# 555-light-buzzer.net
KiCad netlist of a schematic drawn in EAGLE
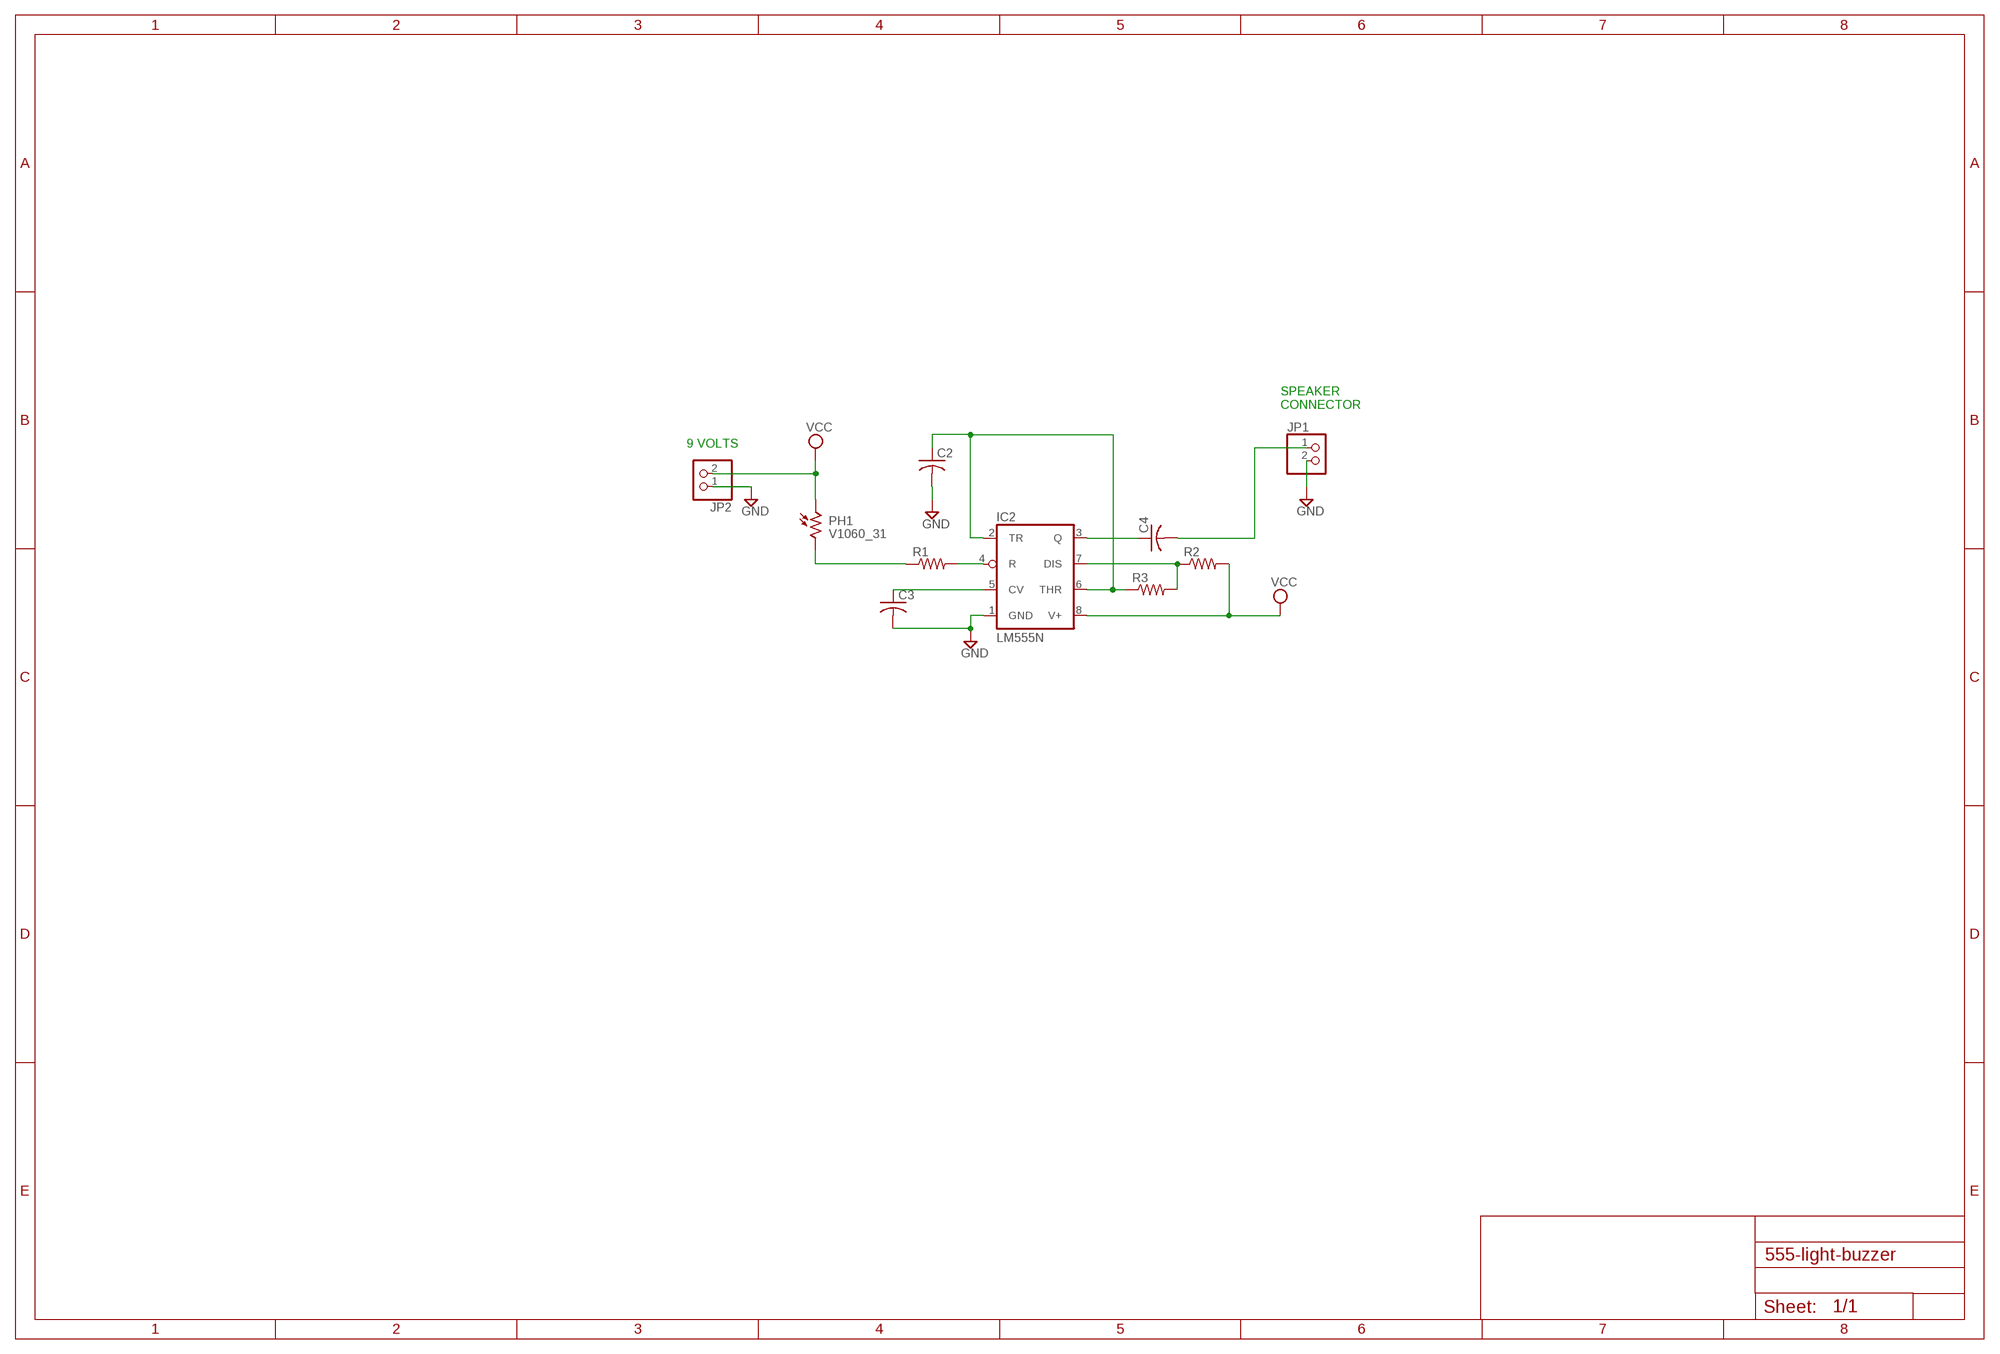
[diagram p0: schematic, sheet 1]

(export (version "E")
  (design (tool "Eeschema 10.0.6"))
  (components
    (comp (ref "C2")
      (value "C-US050-050X075")
      (footprint "eagle-import:C050-050X075")
      (libsource (lib "eagle-import") (part "C-US050-050X075"))
    )
    (comp (ref "C3")
      (value "C-US050-050X075")
      (footprint "eagle-import:C050-050X075")
      (libsource (lib "eagle-import") (part "C-US050-050X075"))
    )
    (comp (ref "C4")
      (value "C-US050-050X075")
      (footprint "eagle-import:C050-050X075")
      (libsource (lib "eagle-import") (part "C-US050-050X075"))
    )
    (comp (ref "IC2")
      (value "LM555N")
      (footprint "eagle-import:DIL08")
      (libsource (lib "eagle-import") (part "555NLM"))
    )
    (comp (ref "JP1")
      (value "PINHD-1X2")
      (footprint "eagle-import:1X02")
      (libsource (lib "eagle-import") (part "PINHD-1X2"))
    )
    (comp (ref "JP2")
      (value "PINHD-1X2")
      (footprint "eagle-import:1X02")
      (libsource (lib "eagle-import") (part "PINHD-1X2"))
    )
    (comp (ref "PH1")
      (value "V1060_31")
      (footprint "eagle-import:TO-5_V10")
      (libsource (lib "eagle-import") (part "?1060V_31"))
    )
    (comp (ref "R1")
      (value "R-US_0207/10")
      (footprint "eagle-import:0207_10")
      (libsource (lib "eagle-import") (part "R-US_0207/10"))
    )
    (comp (ref "R2")
      (value "R-US_0207/10")
      (footprint "eagle-import:0207_10")
      (libsource (lib "eagle-import") (part "R-US_0207/10"))
    )
    (comp (ref "R3")
      (value "R-US_0207/10")
      (footprint "eagle-import:0207_10")
      (libsource (lib "eagle-import") (part "R-US_0207/10"))
    )
  )
  (nets
    (net (code "1") (name "GND") (class "Default")
      (node (ref "C2") (pin "2") (pinfunction "2_2") (pintype "passive"))
      (node (ref "C3") (pin "2") (pinfunction "2_2") (pintype "passive"))
      (node (ref "IC2") (pin "1") (pinfunction "GND_1") (pintype "power_in"))
      (node (ref "JP1") (pin "2") (pinfunction "2_2") (pintype "passive"))
      (node (ref "JP2") (pin "1") (pinfunction "1_1") (pintype "passive"))
    )
    (net (code "2") (name "Net-(C4-Pad2)") (class "Default")
      (node (ref "C4") (pin "2") (pinfunction "2_2") (pintype "passive"))
      (node (ref "JP1") (pin "1") (pinfunction "1_1") (pintype "passive"))
    )
    (net (code "3") (name "Net-(IC2-CV)") (class "Default")
      (node (ref "C3") (pin "1") (pinfunction "1_1") (pintype "passive"))
      (node (ref "IC2") (pin "5") (pinfunction "CV_5") (pintype "input"))
    )
    (net (code "4") (name "Net-(IC2-DIS)") (class "Default")
      (node (ref "IC2") (pin "7") (pinfunction "DIS_7") (pintype "input"))
      (node (ref "R2") (pin "1") (pinfunction "1_1") (pintype "passive"))
      (node (ref "R3") (pin "2") (pinfunction "2_2") (pintype "passive"))
    )
    (net (code "5") (name "Net-(IC2-Q)") (class "Default")
      (node (ref "C4") (pin "1") (pinfunction "1_1") (pintype "passive"))
      (node (ref "IC2") (pin "3") (pinfunction "Q_3") (pintype "output"))
    )
    (net (code "6") (name "Net-(IC2-R)") (class "Default")
      (node (ref "IC2") (pin "4") (pinfunction "R_4") (pintype "input"))
      (node (ref "R1") (pin "2") (pinfunction "2_2") (pintype "passive"))
    )
    (net (code "7") (name "Net-(IC2-THR)") (class "Default")
      (node (ref "C2") (pin "1") (pinfunction "1_1") (pintype "passive"))
      (node (ref "IC2") (pin "2") (pinfunction "TR_2") (pintype "input"))
      (node (ref "IC2") (pin "6") (pinfunction "THR_6") (pintype "input"))
      (node (ref "R3") (pin "1") (pinfunction "1_1") (pintype "passive"))
    )
    (net (code "8") (name "Net-(PH1-Pad2)") (class "Default")
      (node (ref "PH1") (pin "2") (pinfunction "2_2") (pintype "passive"))
      (node (ref "R1") (pin "1") (pinfunction "1_1") (pintype "passive"))
    )
    (net (code "9") (name "VCC") (class "Default")
      (node (ref "IC2") (pin "8") (pinfunction "V+_8") (pintype "power_in"))
      (node (ref "JP2") (pin "2") (pinfunction "2_2") (pintype "passive"))
      (node (ref "PH1") (pin "1") (pinfunction "1_1") (pintype "passive"))
      (node (ref "R2") (pin "2") (pinfunction "2_2") (pintype "passive"))
    )
  )
)
